# esquema_TTH_v03.net
KiCad netlist of a schematic drawn in EAGLE
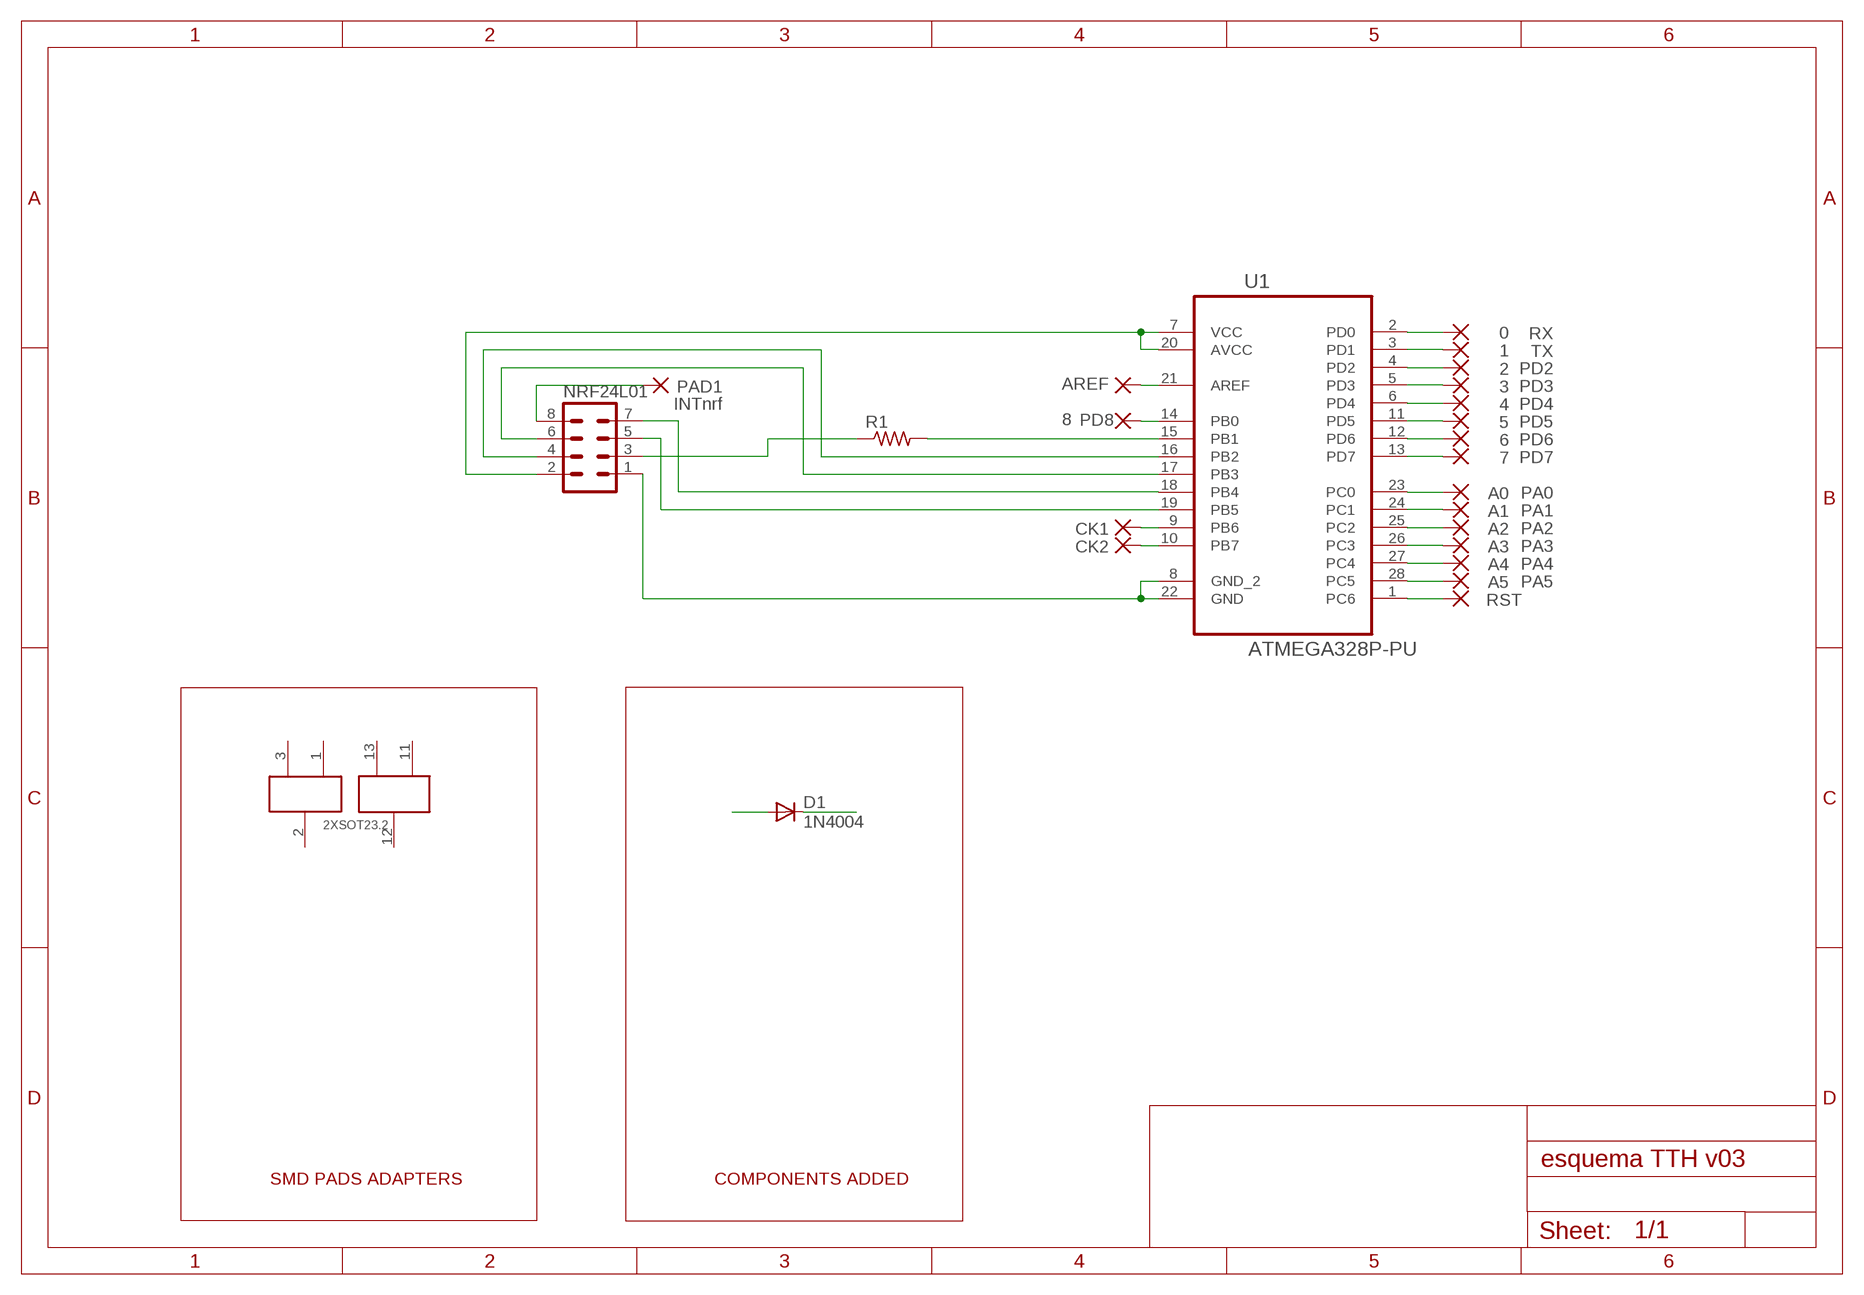
[diagram p0: schematic, sheet 1]

(export (version "E")
  (design (tool "Eeschema 10.0.6"))
  (components
    (comp (ref "2")
      (value "PD2")
      (footprint "eagle-import:2,15_1,0")
      (libsource (lib "eagle-import") (part "2,15/1,0"))
    )
    (comp (ref "3")
      (value "PD3")
      (footprint "eagle-import:2,15_1,0")
      (libsource (lib "eagle-import") (part "2,15/1,0"))
    )
    (comp (ref "4")
      (value "PD4")
      (footprint "eagle-import:2,15_1,0")
      (libsource (lib "eagle-import") (part "2,15/1,0"))
    )
    (comp (ref "5")
      (value "PD5")
      (footprint "eagle-import:2,15_1,0")
      (libsource (lib "eagle-import") (part "2,15/1,0"))
    )
    (comp (ref "6")
      (value "PD6")
      (footprint "eagle-import:2,15_1,0")
      (libsource (lib "eagle-import") (part "2,15/1,0"))
    )
    (comp (ref "7")
      (value "PD7")
      (footprint "eagle-import:2,15_1,0")
      (libsource (lib "eagle-import") (part "2,15/1,0"))
    )
    (comp (ref "8")
      (value "PD8")
      (footprint "eagle-import:2,15_1,0")
      (libsource (lib "eagle-import") (part "2,15/1,0"))
    )
    (comp (ref "A0")
      (value "PA0")
      (footprint "eagle-import:2,15_1,0")
      (libsource (lib "eagle-import") (part "2,15/1,0"))
    )
    (comp (ref "A1")
      (value "PA1")
      (footprint "eagle-import:2,15_1,0")
      (libsource (lib "eagle-import") (part "2,15/1,0"))
    )
    (comp (ref "A2")
      (value "PA2")
      (footprint "eagle-import:2,15_1,0")
      (libsource (lib "eagle-import") (part "2,15/1,0"))
    )
    (comp (ref "A3")
      (value "PA3")
      (footprint "eagle-import:2,15_1,0")
      (libsource (lib "eagle-import") (part "2,15/1,0"))
    )
    (comp (ref "A4")
      (value "PA4")
      (footprint "eagle-import:2,15_1,0")
      (libsource (lib "eagle-import") (part "2,15/1,0"))
    )
    (comp (ref "A5")
      (value "PA5")
      (footprint "eagle-import:2,15_1,0")
      (libsource (lib "eagle-import") (part "2,15/1,0"))
    )
    (comp (ref "AREF")
      (value "2,15/1,0")
      (footprint "eagle-import:2,15_1,0")
      (libsource (lib "eagle-import") (part "2,15/1,0"))
    )
    (comp (ref "CK1")
      (value "2,15/1,0")
      (footprint "eagle-import:2,15_1,0")
      (libsource (lib "eagle-import") (part "2,15/1,0"))
    )
    (comp (ref "CK2")
      (value "2,15/1,0")
      (footprint "eagle-import:2,15_1,0")
      (libsource (lib "eagle-import") (part "2,15/1,0"))
    )
    (comp (ref "D1")
      (value "1N4004")
      (footprint "eagle-import:DO41-10")
      (libsource (lib "eagle-import") (part "1N4004"))
    )
    (comp (ref "NRF24L01")
      (value "MA04-2")
      (footprint "eagle-import:MA04-2")
      (libsource (lib "eagle-import") (part "MA04-2"))
    )
    (comp (ref "PAD1")
      (value "INTnrf")
      (footprint "eagle-import:2,15_1,0")
      (libsource (lib "eagle-import") (part "2,15/1,0"))
    )
    (comp (ref "R1")
      (value "R-US_0207/10")
      (footprint "eagle-import:0207_10")
      (libsource (lib "eagle-import") (part "R-US_0207/10"))
    )
    (comp (ref "RST")
      (value "2,15/1,0")
      (footprint "eagle-import:2,15_1,0")
      (libsource (lib "eagle-import") (part "2,15/1,0"))
    )
    (comp (ref "RX")
      (value "0")
      (footprint "eagle-import:2,15_1,0")
      (libsource (lib "eagle-import") (part "2,15/1,0"))
    )
    (comp (ref "TX")
      (value "1")
      (footprint "eagle-import:2,15_1,0")
      (libsource (lib "eagle-import") (part "2,15/1,0"))
    )
    (comp (ref "U$2")
      (value "2XSOT23.2")
      (footprint "eagle-import:SOT23.5")
      (libsource (lib "eagle-import") (part "2XSOT23.2"))
    )
    (comp (ref "U1")
      (value "ATMEGA328P-PU")
      (footprint "eagle-import:DIP254P762X457-28")
      (libsource (lib "eagle-import") (part "ATMEGA328P-PU"))
    )
  )
  (nets
    (net (code "1") (name "Net-(2-P)") (class "Default")
      (node (ref "2") (pin "1") (pinfunction "P_1") (pintype "passive"))
      (node (ref "U1") (pin "4") (pinfunction "PD2_4") (pintype "bidirectional"))
    )
    (net (code "2") (name "Net-(3-P)") (class "Default")
      (node (ref "3") (pin "1") (pinfunction "P_1") (pintype "passive"))
      (node (ref "U1") (pin "5") (pinfunction "PD3_5") (pintype "bidirectional"))
    )
    (net (code "3") (name "Net-(4-P)") (class "Default")
      (node (ref "4") (pin "1") (pinfunction "P_1") (pintype "passive"))
      (node (ref "U1") (pin "6") (pinfunction "PD4_6") (pintype "bidirectional"))
    )
    (net (code "4") (name "Net-(5-P)") (class "Default")
      (node (ref "5") (pin "1") (pinfunction "P_1") (pintype "passive"))
      (node (ref "U1") (pin "11") (pinfunction "PD5_11") (pintype "bidirectional"))
    )
    (net (code "5") (name "Net-(6-P)") (class "Default")
      (node (ref "6") (pin "1") (pinfunction "P_1") (pintype "passive"))
      (node (ref "U1") (pin "12") (pinfunction "PD6_12") (pintype "bidirectional"))
    )
    (net (code "6") (name "Net-(7-P)") (class "Default")
      (node (ref "7") (pin "1") (pinfunction "P_1") (pintype "passive"))
      (node (ref "U1") (pin "13") (pinfunction "PD7_13") (pintype "bidirectional"))
    )
    (net (code "7") (name "Net-(8-P)") (class "Default")
      (node (ref "8") (pin "1") (pinfunction "P_1") (pintype "passive"))
      (node (ref "U1") (pin "14") (pinfunction "PB0_14") (pintype "bidirectional"))
    )
    (net (code "8") (name "Net-(A0-P)") (class "Default")
      (node (ref "A0") (pin "1") (pinfunction "P_1") (pintype "passive"))
      (node (ref "U1") (pin "23") (pinfunction "PC0_23") (pintype "bidirectional"))
    )
    (net (code "9") (name "Net-(A1-P)") (class "Default")
      (node (ref "A1") (pin "1") (pinfunction "P_1") (pintype "passive"))
      (node (ref "U1") (pin "24") (pinfunction "PC1_24") (pintype "bidirectional"))
    )
    (net (code "10") (name "Net-(A2-P)") (class "Default")
      (node (ref "A2") (pin "1") (pinfunction "P_1") (pintype "passive"))
      (node (ref "U1") (pin "25") (pinfunction "PC2_25") (pintype "bidirectional"))
    )
    (net (code "11") (name "Net-(A3-P)") (class "Default")
      (node (ref "A3") (pin "1") (pinfunction "P_1") (pintype "passive"))
      (node (ref "U1") (pin "26") (pinfunction "PC3_26") (pintype "bidirectional"))
    )
    (net (code "12") (name "Net-(A4-P)") (class "Default")
      (node (ref "A4") (pin "1") (pinfunction "P_1") (pintype "passive"))
      (node (ref "U1") (pin "27") (pinfunction "PC4_27") (pintype "bidirectional"))
    )
    (net (code "13") (name "Net-(A5-P)") (class "Default")
      (node (ref "A5") (pin "1") (pinfunction "P_1") (pintype "passive"))
      (node (ref "U1") (pin "28") (pinfunction "PC5_28") (pintype "bidirectional"))
    )
    (net (code "14") (name "Net-(AREF-P)") (class "Default")
      (node (ref "AREF") (pin "1") (pinfunction "P_1") (pintype "passive"))
      (node (ref "U1") (pin "21") (pinfunction "AREF_21") (pintype "input"))
    )
    (net (code "15") (name "Net-(CK1-P)") (class "Default")
      (node (ref "CK1") (pin "1") (pinfunction "P_1") (pintype "passive"))
      (node (ref "U1") (pin "9") (pinfunction "PB6_9") (pintype "bidirectional"))
    )
    (net (code "16") (name "Net-(CK2-P)") (class "Default")
      (node (ref "CK2") (pin "1") (pinfunction "P_1") (pintype "passive"))
      (node (ref "U1") (pin "10") (pinfunction "PB7_10") (pintype "bidirectional"))
    )
    (net (code "17") (name "Net-(NRF24L01-Pad3)") (class "Default")
      (node (ref "NRF24L01") (pin "3") (pinfunction "3_3") (pintype "passive"))
      (node (ref "R1") (pin "1") (pinfunction "1_1") (pintype "passive"))
    )
    (net (code "18") (name "Net-(PAD1-P)") (class "Default")
      (node (ref "NRF24L01") (pin "8") (pinfunction "8_8") (pintype "passive"))
      (node (ref "PAD1") (pin "1") (pinfunction "P_1") (pintype "passive"))
    )
    (net (code "19") (name "Net-(RST-P)") (class "Default")
      (node (ref "RST") (pin "1") (pinfunction "P_1") (pintype "passive"))
      (node (ref "U1") (pin "1") (pinfunction "PC6_1") (pintype "bidirectional"))
    )
    (net (code "20") (name "Net-(RX-P)") (class "Default")
      (node (ref "RX") (pin "1") (pinfunction "P_1") (pintype "passive"))
      (node (ref "U1") (pin "2") (pinfunction "PD0_2") (pintype "bidirectional"))
    )
    (net (code "21") (name "Net-(TX-P)") (class "Default")
      (node (ref "TX") (pin "1") (pinfunction "P_1") (pintype "passive"))
      (node (ref "U1") (pin "3") (pinfunction "PD1_3") (pintype "bidirectional"))
    )
    (net (code "22") (name "Net-(U1-AVCC)") (class "Default")
      (node (ref "NRF24L01") (pin "2") (pinfunction "2_2") (pintype "passive"))
      (node (ref "U1") (pin "20") (pinfunction "AVCC_20") (pintype "power_in"))
      (node (ref "U1") (pin "7") (pinfunction "VCC_7") (pintype "power_in"))
    )
    (net (code "23") (name "Net-(U1-GND)") (class "Default")
      (node (ref "NRF24L01") (pin "1") (pinfunction "1_1") (pintype "passive"))
      (node (ref "U1") (pin "22") (pinfunction "GND_22") (pintype "passive"))
      (node (ref "U1") (pin "8") (pinfunction "GND_2_8") (pintype "passive"))
    )
    (net (code "24") (name "Net-(U1-PB1)") (class "Default")
      (node (ref "R1") (pin "2") (pinfunction "2_2") (pintype "passive"))
      (node (ref "U1") (pin "15") (pinfunction "PB1_15") (pintype "bidirectional"))
    )
    (net (code "25") (name "Net-(U1-PB2)") (class "Default")
      (node (ref "NRF24L01") (pin "4") (pinfunction "4_4") (pintype "passive"))
      (node (ref "U1") (pin "16") (pinfunction "PB2_16") (pintype "bidirectional"))
    )
    (net (code "26") (name "Net-(U1-PB3)") (class "Default")
      (node (ref "NRF24L01") (pin "6") (pinfunction "6_6") (pintype "passive"))
      (node (ref "U1") (pin "17") (pinfunction "PB3_17") (pintype "bidirectional"))
    )
    (net (code "27") (name "Net-(U1-PB4)") (class "Default")
      (node (ref "NRF24L01") (pin "7") (pinfunction "7_7") (pintype "passive"))
      (node (ref "U1") (pin "18") (pinfunction "PB4_18") (pintype "bidirectional"))
    )
    (net (code "28") (name "Net-(U1-PB5)") (class "Default")
      (node (ref "NRF24L01") (pin "5") (pinfunction "5_5") (pintype "passive"))
      (node (ref "U1") (pin "19") (pinfunction "PB5_19") (pintype "bidirectional"))
    )
    (net (code "29") (name "unconnected-(D1-PadA)") (class "Default")
      (node (ref "D1") (pin "A") (pinfunction "A_A") (pintype "passive"))
    )
    (net (code "30") (name "unconnected-(D1-PadC)") (class "Default")
      (node (ref "D1") (pin "C") (pinfunction "C_C") (pintype "passive"))
    )
    (net (code "31") (name "unconnected-(U$2-Pad1)") (class "Default")
      (node (ref "U$2") (pin "1") (pinfunction "1_1") (pintype "bidirectional"))
    )
    (net (code "32") (name "unconnected-(U$2-Pad2)") (class "Default")
      (node (ref "U$2") (pin "2") (pinfunction "2_2") (pintype "bidirectional"))
    )
    (net (code "33") (name "unconnected-(U$2-Pad3)") (class "Default")
      (node (ref "U$2") (pin "3") (pinfunction "3_3") (pintype "bidirectional"))
    )
    (net (code "34") (name "unconnected-(U$2-Pad11)") (class "Default")
      (node (ref "U$2") (pin "11") (pinfunction "11_11") (pintype "bidirectional"))
    )
    (net (code "35") (name "unconnected-(U$2-Pad12)") (class "Default")
      (node (ref "U$2") (pin "12") (pinfunction "12_12") (pintype "bidirectional"))
    )
    (net (code "36") (name "unconnected-(U$2-Pad13)") (class "Default")
      (node (ref "U$2") (pin "13") (pinfunction "13_13") (pintype "bidirectional"))
    )
  )
)
